# ASM001-design-4.net
KiCad netlist of a schematic drawn in Altium Designer
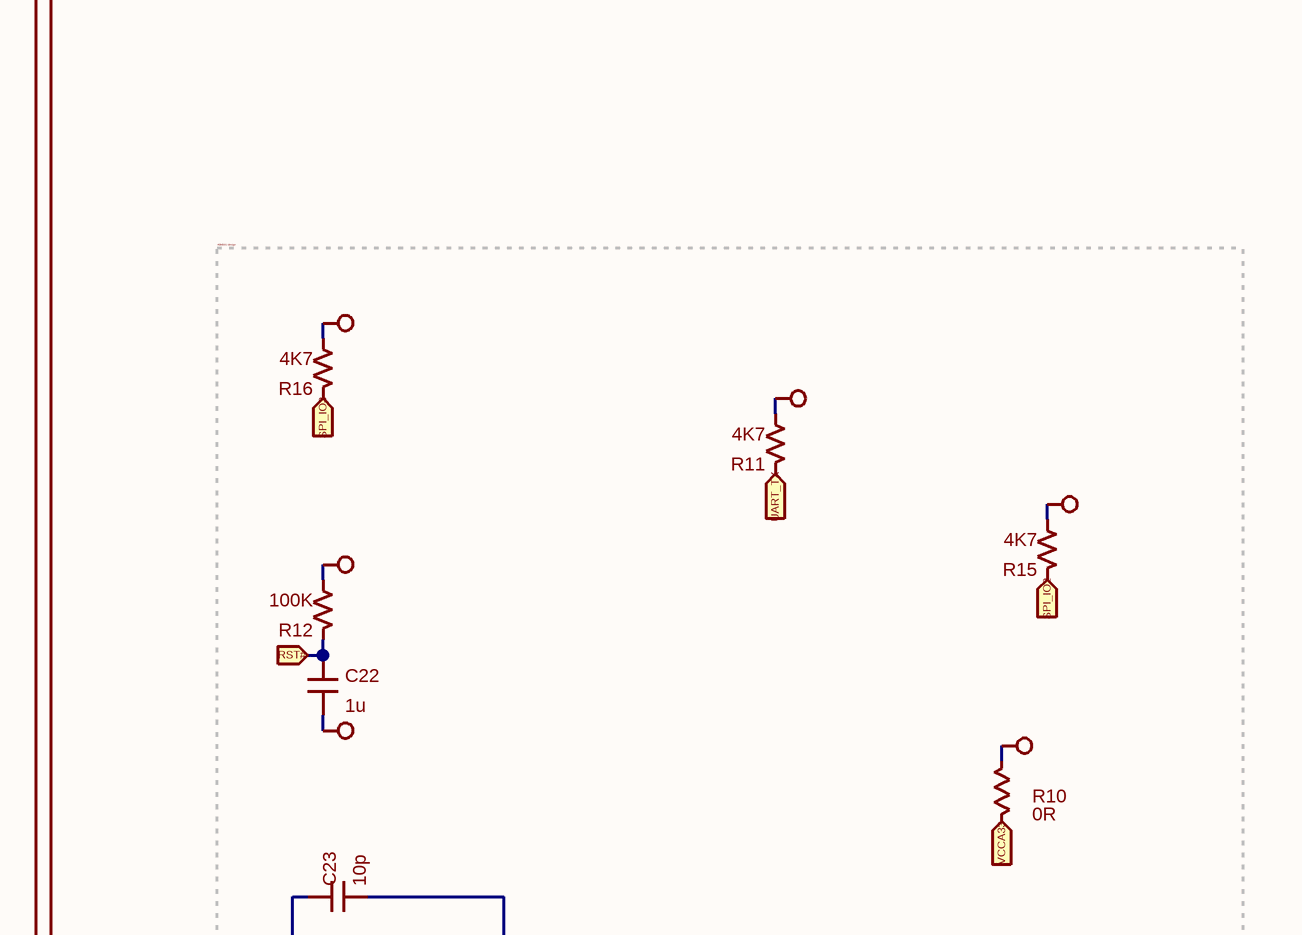
[diagram p0: ASM001-design-4.SchDoc, centre column 1 of 4]
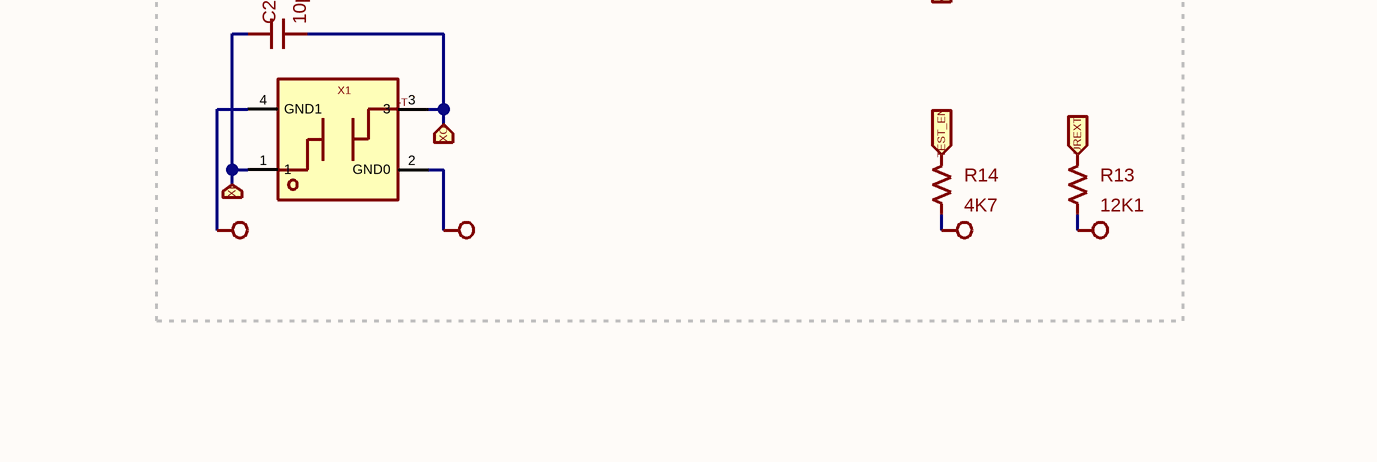
[diagram p1: ASM001-design-4.SchDoc, bottom column 1 of 4]
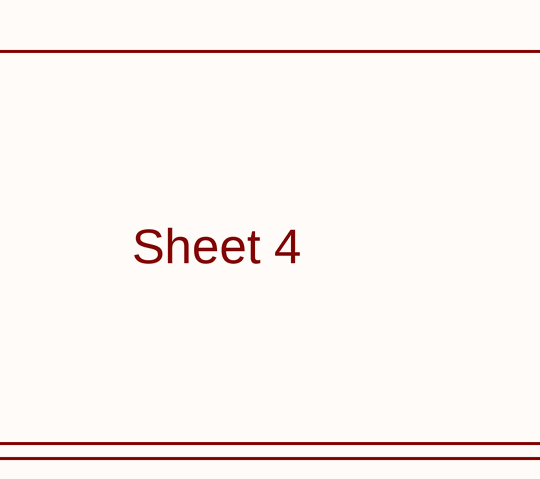
[diagram p2: ASM001-design-4.SchDoc, bottom column 4 of 4]

(export (version "E")
  (design (tool "Eeschema 10.0.6"))
  (components
    (comp (ref "C22")
      (value "1u")
      (footprint "Pkg0402$2")
      (description "C1518208")
      (fields
        (field (name "TOLERANCE") "Toleranced(9.0e-007 <= 1.0e-006 <= 1.1e-006)")
        (field (name "MANUFACTURER") "Murata Electronics")
      )
      (libsource (lib "ASM001-design") (part "C1518208"))
    )
    (comp (ref "C23")
      (value "10p")
      (footprint "LP")
      (description "my_capacitor")
      (fields
        (field (name "TOLERANCE") "Toleranced(9.9e-012 <= 1.0e-011 <= 1.01e-011)")
        (field (name "MPN") "04025A100FAT2A")
      )
      (libsource (lib "ASM001-design") (part "my_capacitor"))
    )
    (comp (ref "R10")
      (value "0R")
      (footprint "SMT_0201")
      (description "C106228")
      (fields (field (name "MPN") "RC0201JR-070RL") (field (name "MANUFACTURER") "YAGEO"))
      (libsource (lib "ASM001-design") (part "C106228"))
    )
    (comp (ref "R11")
      (value "4K7")
      (footprint "Pkg0402$10")
      (description "my_resistor$7")
      (fields
        (field (name "MPN") "SCR0402F4K7")
        (field (name "TOLERANCE") "Toleranced(4653.0 <= 4700.0 <= 4747.0)")
      )
      (libsource (lib "ASM001-design") (part "my_resistor$7"))
    )
    (comp (ref "R12")
      (value "100K")
      (footprint "Pkg0201$2")
      (description "my_resistor$8")
      (fields
        (field (name "MPN") "SC0201F1003G1BNRH")
        (field (name "TOLERANCE") "Toleranced(99000.0 <= 100000.0 <= 101000.0)")
      )
      (libsource (lib "ASM001-design") (part "my_resistor$8"))
    )
    (comp (ref "R13")
      (value "12K1")
      (footprint "Pkg0402$5")
      (description "C168199")
      (fields
        (field (name "TOLERANCE") "Toleranced(11979.0 <= 12100.0 <= 12221.0)")
        (field (name "MANUFACTURER") "Walsin Technology Corporation")
      )
      (libsource (lib "ASM001-design") (part "C168199"))
    )
    (comp (ref "R14")
      (value "4K7")
      (footprint "Pkg0402$10")
      (description "my_resistor$7")
      (fields
        (field (name "MPN") "SCR0402F4K7")
        (field (name "TOLERANCE") "Toleranced(4653.0 <= 4700.0 <= 4747.0)")
      )
      (libsource (lib "") (part "my_resistor$7_1"))
    )
    (comp (ref "R15")
      (value "4K7")
      (footprint "Pkg0402$10")
      (description "my_resistor$7")
      (fields
        (field (name "MPN") "SCR0402F4K7")
        (field (name "TOLERANCE") "Toleranced(4653.0 <= 4700.0 <= 4747.0)")
      )
      (libsource (lib "ASM001-design") (part "my_resistor$7"))
    )
    (comp (ref "R16")
      (value "4K7")
      (footprint "Pkg0402$10")
      (description "my_resistor$7")
      (fields
        (field (name "MPN") "SCR0402F4K7")
        (field (name "TOLERANCE") "Toleranced(4653.0 <= 4700.0 <= 4747.0)")
      )
      (libsource (lib "ASM001-design") (part "my_resistor$7"))
    )
    (comp (ref "X1")
      (value "ABMM2-25.000MHZ-D1-T")
      (footprint "LP$2")
      (description "C1985419")
      (fields (field (name "MANUFACTURER") "ABRACON"))
      (libsource (lib "ASM001-design") (part "C1985419"))
    )
  )
  (nets
    (net (code "1") (name "/RST#") (class "Default")
      (node (ref "C22") (pin "1") (pinfunction "1_1") (pintype "passive"))
      (node (ref "R12") (pin "1") (pinfunction "1_1") (pintype "passive"))
    )
    (net (code "2") (name "/SPI_IO2") (class "Default")
      (node (ref "R15") (pin "1") (pinfunction "1_1") (pintype "passive"))
    )
    (net (code "3") (name "/SPI_IO3") (class "Default")
      (node (ref "R16") (pin "1") (pinfunction "1_1") (pintype "passive"))
    )
    (net (code "4") (name "/TEST_EN") (class "Default")
      (node (ref "R14") (pin "1") (pinfunction "1_1") (pintype "passive"))
    )
    (net (code "5") (name "/UART_TX") (class "Default")
      (node (ref "R11") (pin "1") (pinfunction "1_1") (pintype "passive"))
    )
    (net (code "6") (name "/UREXT") (class "Default")
      (node (ref "R13") (pin "1") (pinfunction "1_1") (pintype "passive"))
    )
    (net (code "7") (name "/VCCA33") (class "Default")
      (node (ref "R10") (pin "2") (pinfunction "2_2") (pintype "passive"))
    )
    (net (code "8") (name "/XI") (class "Default")
      (node (ref "C23") (pin "1") (pinfunction "1_1") (pintype "passive"))
      (node (ref "X1") (pin "1") (pinfunction "1_1") (pintype "passive"))
    )
    (net (code "9") (name "/XO") (class "Default")
      (node (ref "C23") (pin "2") (pinfunction "2_2") (pintype "passive"))
      (node (ref "X1") (pin "3") (pinfunction "3_3") (pintype "passive"))
    )
    (net (code "10") (name "<NO NET>") (class "Default")
      (node (ref "C22") (pin "2") (pinfunction "2_2") (pintype "passive"))
      (node (ref "R10") (pin "1") (pinfunction "1_1") (pintype "passive"))
      (node (ref "R11") (pin "2") (pinfunction "2_2") (pintype "passive"))
      (node (ref "R12") (pin "2") (pinfunction "2_2") (pintype "passive"))
      (node (ref "R13") (pin "2") (pinfunction "2_2") (pintype "passive"))
      (node (ref "R14") (pin "2") (pinfunction "2_2") (pintype "passive"))
      (node (ref "R15") (pin "2") (pinfunction "2_2") (pintype "passive"))
      (node (ref "R16") (pin "2") (pinfunction "2_2") (pintype "passive"))
      (node (ref "X1") (pin "2") (pinfunction "GND0_2") (pintype "passive"))
      (node (ref "X1") (pin "4") (pinfunction "GND1_4") (pintype "passive"))
    )
  )
)
